# yoav-mlotok-card.net
KiCad netlist of a schematic drawn in EasyEDA Pro
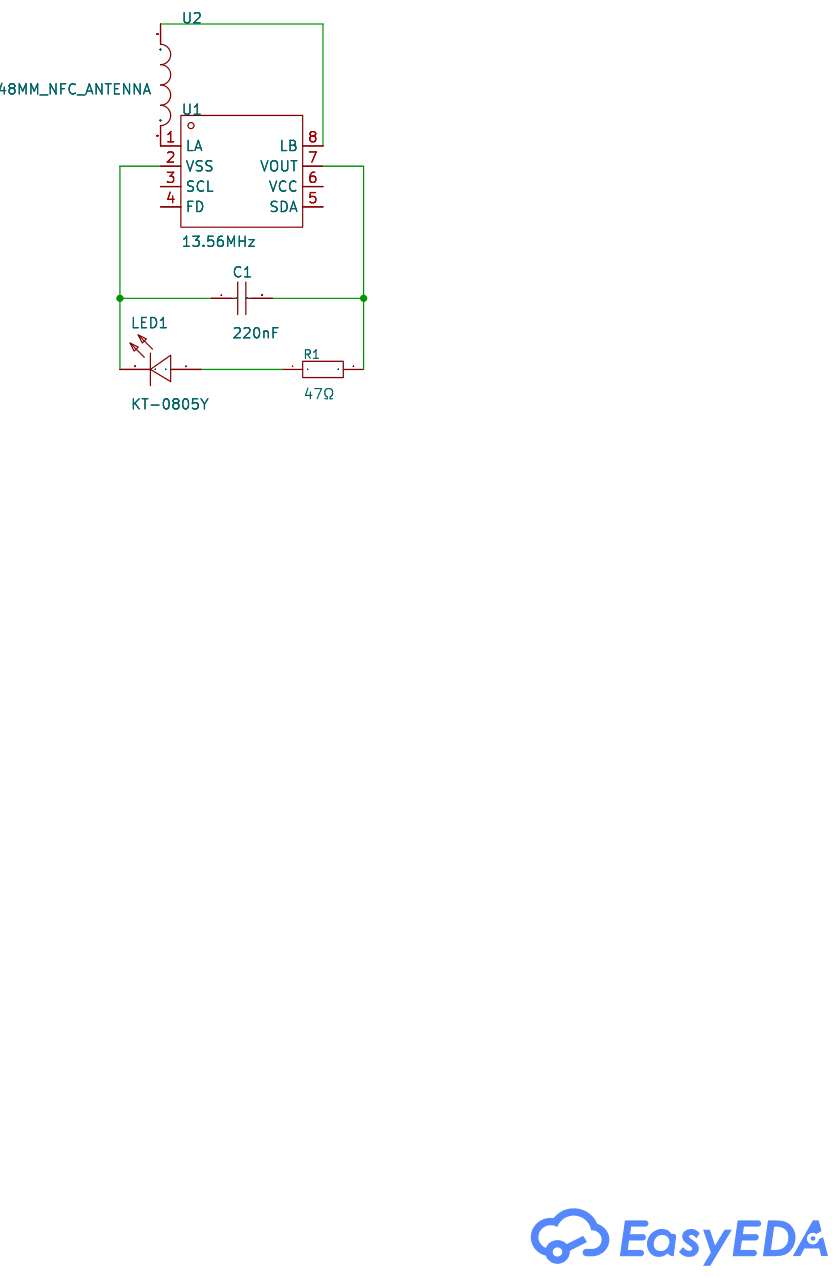
[diagram p0: schematic sheet]

(export (version "E")
  (design (tool "Eeschema 10.0.6"))
  (components
    (comp (ref "C1")
      (value "220nF")
      (footprint "easyedapro:C0603")
      (description "容值:220nF;精度:±10%;额定电压:25V;材质(温度系数):X7R;")
      (fields
        (field (name "Manufacturer Part") "CL10B224KA8NNNC")
        (field (name "Manufacturer") "SAMSUNG(三星)")
      )
      (libsource (lib "easyedapro") (part "CL10B224KA8NNNC"))
    )
    (comp (ref "LED1")
      (value "KT-0805Y")
      (footprint "easyedapro:LED0805-R-RD")
      (fields (field (name "Manufacturer") "KENTO"))
      (libsource (lib "easyedapro") (part "whiteLEDSMD"))
    )
    (comp (ref "R1")
      (value "47Ω")
      (footprint "easyedapro:R0603")
      (fields
        (field (name "Manufacturer Part") "0603WAF470JT5E")
        (field (name "Manufacturer") "UNI-ROYAL(厚声)")
      )
      (libsource (lib "easyedapro") (part "0603WAF470JT5E"))
    )
    (comp (ref "U1")
      (value "13.56MHz")
      (footprint "easyedapro:XQFN-8_L1.6-W1.6-P0.50-BL_NT3H2111W0FHKH")
      (fields (field (name "Manufacturer Part") "NT3H2111W0FHKH") (field (name "Manufacturer") "NXP(恩智浦)"))
      (libsource (lib "easyedapro") (part "NT3H2111W0FHKH"))
    )
    (comp (ref "U2")
      (value "25X48MM_NFC_ANTENNA")
      (footprint "easyedapro:25X48MM_NFC_ANTENNA")
      (libsource (lib "easyedapro") (part "25X48MM_NFC_ANTENNA"))
    )
  )
  (nets
    (net (code "1") (name "Net-(LED1-A)") (class "Default")
      (node (ref "LED1") (pin "1") (pinfunction "A_1") (pintype "unspecified"))
      (node (ref "R1") (pin "1") (pinfunction "1_1") (pintype "input"))
    )
    (net (code "2") (name "Net-(LED1-K)") (class "Default")
      (node (ref "C1") (pin "1") (pinfunction "1_1") (pintype "input"))
      (node (ref "LED1") (pin "2") (pinfunction "K_2") (pintype "unspecified"))
      (node (ref "U1") (pin "2") (pinfunction "VSS_2") (pintype "unspecified"))
    )
    (net (code "3") (name "Net-(U1-LA)") (class "Default")
      (node (ref "U1") (pin "1") (pinfunction "LA_1") (pintype "unspecified"))
      (node (ref "U2") (pin "P$2") (pinfunction "P$2_P$2") (pintype "bidirectional"))
    )
    (net (code "4") (name "Net-(U1-LB)") (class "Default")
      (node (ref "U1") (pin "8") (pinfunction "LB_8") (pintype "unspecified"))
      (node (ref "U2") (pin "P$1") (pinfunction "P$1_P$1") (pintype "bidirectional"))
    )
    (net (code "5") (name "Net-(U1-VOUT)") (class "Default")
      (node (ref "C1") (pin "2") (pinfunction "2_2") (pintype "input"))
      (node (ref "R1") (pin "2") (pinfunction "2_2") (pintype "input"))
      (node (ref "U1") (pin "7") (pinfunction "VOUT_7") (pintype "unspecified"))
    )
    (net (code "6") (name "unconnected-(U1-FD-Pad4)") (class "Default")
      (node (ref "U1") (pin "4") (pinfunction "FD_4") (pintype "unspecified"))
    )
    (net (code "7") (name "unconnected-(U1-SCL-Pad3)") (class "Default")
      (node (ref "U1") (pin "3") (pinfunction "SCL_3") (pintype "unspecified"))
    )
    (net (code "8") (name "unconnected-(U1-SDA-Pad5)") (class "Default")
      (node (ref "U1") (pin "5") (pinfunction "SDA_5") (pintype "unspecified"))
    )
    (net (code "9") (name "unconnected-(U1-VCC-Pad6)") (class "Default")
      (node (ref "U1") (pin "6") (pinfunction "VCC_6") (pintype "unspecified"))
    )
  )
)
